# MCU.net
KiCad netlist of a schematic drawn in Altium Designer
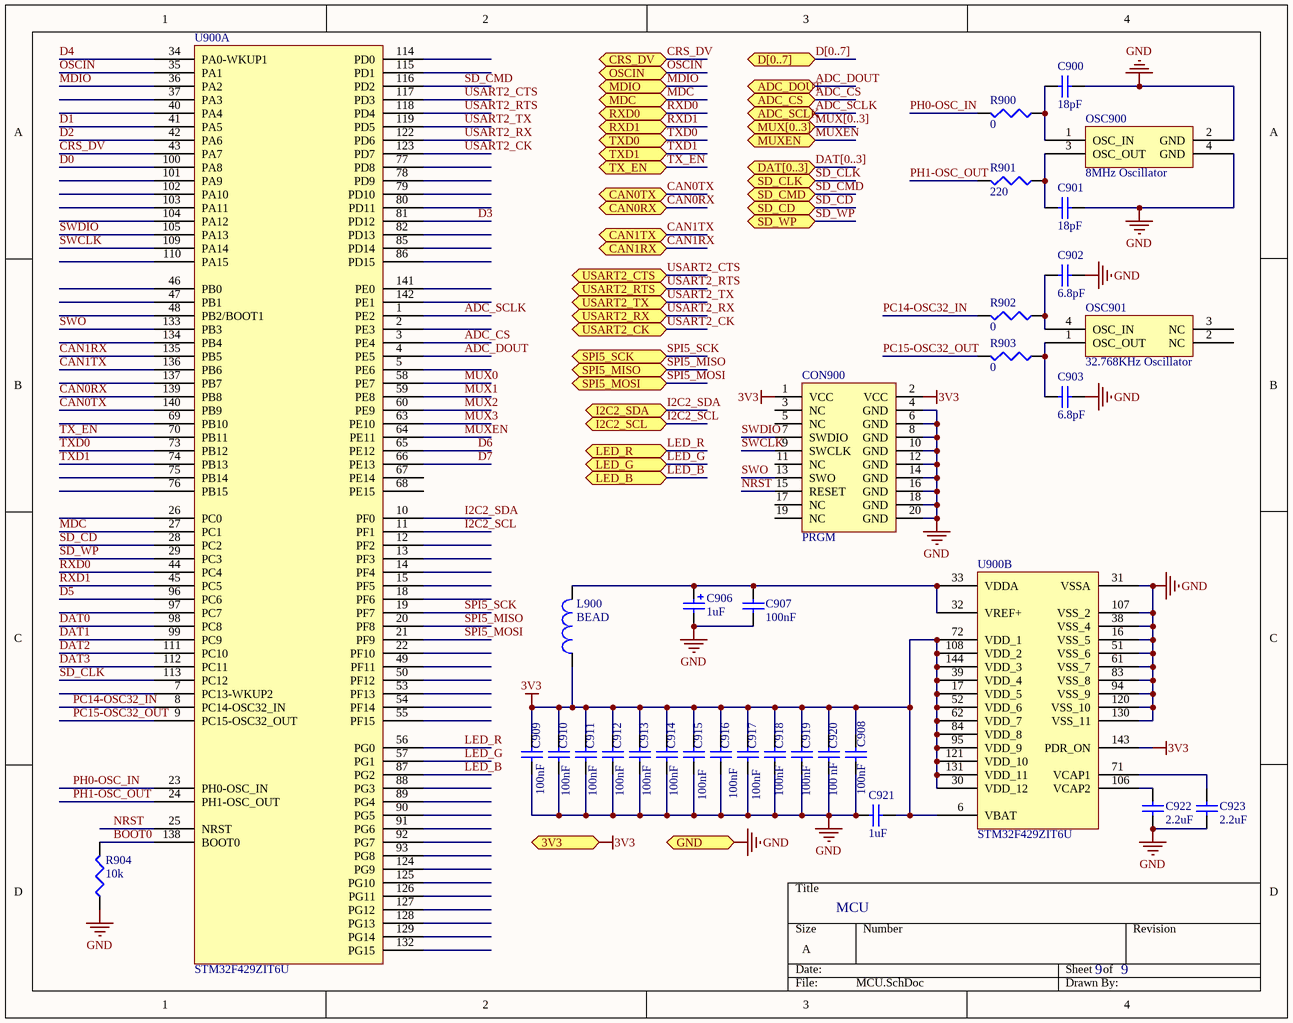
[diagram p0: MCU.SchDoc]

(export (version "E")
  (design (tool "Eeschema 10.0.6"))
  (components
    (comp (ref "C900")
      (value "18pF")
      (footprint "SMD0603")
      (description "Ceramic Chip Capacitor")
      (fields (field (name "Comment") "Cap"))
      (libsource (lib "Components") (part "Capacitor Ceramic"))
    )
    (comp (ref "C901")
      (value "18pF")
      (footprint "SMD0603")
      (description "Ceramic Chip Capacitor")
      (fields (field (name "Comment") "Cap"))
      (libsource (lib "Components") (part "Capacitor Ceramic"))
    )
    (comp (ref "C902")
      (value "6.8pF")
      (footprint "SMD0603")
      (description "Ceramic Chip Capacitor")
      (fields (field (name "Comment") "Cap"))
      (libsource (lib "Components") (part "Capacitor Ceramic"))
    )
    (comp (ref "C903")
      (value "6.8pF")
      (footprint "SMD0603")
      (description "Ceramic Chip Capacitor")
      (fields (field (name "Comment") "Cap"))
      (libsource (lib "Components") (part "Capacitor Ceramic"))
    )
    (comp (ref "C906")
      (value "1uF")
      (footprint "SMD1206 Polarized")
      (description "Polarized Capacitor (Surface Mount)")
      (fields (field (name "Comment") "Cap"))
      (libsource (lib "Components") (part "Capacitor Polarized"))
    )
    (comp (ref "C907")
      (value "100nF")
      (footprint "SMD0603")
      (description "Ceramic Chip Capacitor")
      (fields (field (name "Comment") "Cap"))
      (libsource (lib "Components") (part "Capacitor Ceramic"))
    )
    (comp (ref "C908")
      (value "100nF")
      (footprint "SMD0603")
      (description "Ceramic Chip Capacitor")
      (fields (field (name "Comment") "Cap"))
      (libsource (lib "Components") (part "Capacitor Ceramic"))
    )
    (comp (ref "C909")
      (value "100nF")
      (footprint "SMD0603")
      (description "Ceramic Chip Capacitor")
      (fields (field (name "Comment") "Cap"))
      (libsource (lib "Components") (part "Capacitor Ceramic"))
    )
    (comp (ref "C910")
      (value "100nF")
      (footprint "SMD0603")
      (description "Ceramic Chip Capacitor")
      (fields (field (name "Comment") "Cap"))
      (libsource (lib "Components") (part "Capacitor Ceramic"))
    )
    (comp (ref "C911")
      (value "100nF")
      (footprint "SMD0603")
      (description "Ceramic Chip Capacitor")
      (fields (field (name "Comment") "Cap"))
      (libsource (lib "Components") (part "Capacitor Ceramic"))
    )
    (comp (ref "C912")
      (value "100nF")
      (footprint "SMD0603")
      (description "Ceramic Chip Capacitor")
      (fields (field (name "Comment") "Cap"))
      (libsource (lib "Components") (part "Capacitor Ceramic"))
    )
    (comp (ref "C913")
      (value "100nF")
      (footprint "SMD0603")
      (description "Ceramic Chip Capacitor")
      (fields (field (name "Comment") "Cap"))
      (libsource (lib "Components") (part "Capacitor Ceramic"))
    )
    (comp (ref "C914")
      (value "100nF")
      (footprint "SMD0603")
      (description "Ceramic Chip Capacitor")
      (fields (field (name "Comment") "Cap"))
      (libsource (lib "Components") (part "Capacitor Ceramic"))
    )
    (comp (ref "C915")
      (value "100nF")
      (footprint "SMD0603")
      (description "Ceramic Chip Capacitor")
      (fields (field (name "Comment") "Cap"))
      (libsource (lib "Components") (part "Capacitor Ceramic"))
    )
    (comp (ref "C916")
      (value "100nF")
      (footprint "SMD0603")
      (description "Ceramic Chip Capacitor")
      (fields (field (name "Comment") "Cap"))
      (libsource (lib "Components") (part "Capacitor Ceramic"))
    )
    (comp (ref "C917")
      (value "100nF")
      (footprint "SMD0603")
      (description "Ceramic Chip Capacitor")
      (fields (field (name "Comment") "Cap"))
      (libsource (lib "Components") (part "Capacitor Ceramic"))
    )
    (comp (ref "C918")
      (value "100nF")
      (footprint "SMD0603")
      (description "Ceramic Chip Capacitor")
      (fields (field (name "Comment") "Cap"))
      (libsource (lib "Components") (part "Capacitor Ceramic"))
    )
    (comp (ref "C919")
      (value "100nF")
      (footprint "SMD0603")
      (description "Ceramic Chip Capacitor")
      (fields (field (name "Comment") "Cap"))
      (libsource (lib "Components") (part "Capacitor Ceramic"))
    )
    (comp (ref "C920")
      (value "100 nF")
      (footprint "SMD0603")
      (description "Ceramic Chip Capacitor")
      (fields (field (name "Comment") "Cap"))
      (libsource (lib "Components") (part "Capacitor Ceramic"))
    )
    (comp (ref "C921")
      (value "1uF")
      (footprint "SMD0805")
      (description "Ceramic Chip Capacitor")
      (fields (field (name "Comment") "Cap"))
      (libsource (lib "Components") (part "Capacitor Ceramic"))
    )
    (comp (ref "C922")
      (value "2.2uF")
      (footprint "SMD1206")
      (description "Ceramic Chip Capacitor")
      (fields (field (name "Comment") "Cap"))
      (libsource (lib "Components") (part "Capacitor Ceramic"))
    )
    (comp (ref "C923")
      (value "2.2uF")
      (footprint "SMD1206")
      (description "Ceramic Chip Capacitor")
      (fields (field (name "Comment") "Cap"))
      (libsource (lib "Components") (part "Capacitor Ceramic"))
    )
    (comp (ref "CON900")
      (value "PRGM")
      (footprint "JTAG/SWO-20PIN")
      (libsource (lib "Components") (part "JTAG/SWO-20PIN"))
    )
    (comp (ref "L900")
      (value "BEAD")
      (footprint "SMD0603")
      (description "Ferrite Bead")
      (fields (field (name "PART") "BK1608HS601-TV"))
      (libsource (lib "Components") (part "Chip Ferrite Bead"))
    )
    (comp (ref "OSC900")
      (value "8MHz Oscillator")
      (footprint "ABMM2-OSC")
      (libsource (lib "Components") (part "ABMM2-8.000MHZ-E2-T"))
    )
    (comp (ref "OSC901")
      (value "32.768KHz Oscillator")
      (footprint "MC-306-OSC")
      (description "32.7680kHz Oscillator")
      (libsource (lib "Components") (part "MC-306 32.768K-E3"))
    )
    (comp (ref "R900")
      (value "0")
      (footprint "SMD0603")
      (description "Resistor")
      (fields (field (name "Comment") "Res"))
      (libsource (lib "Components") (part "Resistor"))
    )
    (comp (ref "R901")
      (value "220")
      (footprint "SMD0603")
      (description "Resistor")
      (fields (field (name "Comment") "Res"))
      (libsource (lib "Components") (part "Resistor"))
    )
    (comp (ref "R902")
      (value "0")
      (footprint "SMD0603")
      (description "Resistor")
      (fields (field (name "Comment") "Res"))
      (libsource (lib "Components") (part "Resistor"))
    )
    (comp (ref "R903")
      (value "0")
      (footprint "SMD0603")
      (description "Resistor")
      (fields (field (name "Comment") "Res"))
      (libsource (lib "Components") (part "Resistor"))
    )
    (comp (ref "R904")
      (value "10k")
      (footprint "SMD0603")
      (description "Resistor")
      (fields (field (name "Comment") "Res"))
      (libsource (lib "Components") (part "Resistor"))
    )
    (comp (ref "U900")
      (value "STM32F429ZIT6U")
      (footprint "LQPF144")
      (libsource (lib "Components") (part "STM32F429ZIT6U"))
    )
  )
  (nets
    (net (code "1") (name "/ADC_CS") (class "Default")
      (node (ref "U900") (pin "3") (pinfunction "PE4_3") (pintype "passive"))
    )
    (net (code "2") (name "/ADC_DOUT") (class "Default")
      (node (ref "U900") (pin "4") (pinfunction "PE5_4") (pintype "passive"))
    )
    (net (code "3") (name "/ADC_SCLK") (class "Default")
      (node (ref "U900") (pin "1") (pinfunction "PE2_1") (pintype "passive"))
    )
    (net (code "4") (name "/BOOT0") (class "Default")
      (node (ref "R904") (pin "2") (pinfunction "2_2") (pintype "passive"))
      (node (ref "U900") (pin "138") (pinfunction "BOOT0_138") (pintype "passive"))
    )
    (net (code "5") (name "/CAN0RX") (class "Default")
      (node (ref "U900") (pin "139") (pinfunction "PB8_139") (pintype "passive"))
    )
    (net (code "6") (name "/CAN0TX") (class "Default")
      (node (ref "U900") (pin "140") (pinfunction "PB9_140") (pintype "passive"))
    )
    (net (code "7") (name "/CAN1RX") (class "Default")
      (node (ref "U900") (pin "135") (pinfunction "PB5_135") (pintype "passive"))
    )
    (net (code "8") (name "/CAN1TX") (class "Default")
      (node (ref "U900") (pin "136") (pinfunction "PB6_136") (pintype "passive"))
    )
    (net (code "9") (name "/CRS_DV") (class "Default")
      (node (ref "U900") (pin "43") (pinfunction "PA7_43") (pintype "passive"))
    )
    (net (code "10") (name "/D0") (class "Default")
      (node (ref "U900") (pin "100") (pinfunction "PA8_100") (pintype "passive"))
    )
    (net (code "11") (name "/D1") (class "Default")
      (node (ref "U900") (pin "41") (pinfunction "PA5_41") (pintype "passive"))
    )
    (net (code "12") (name "/D2") (class "Default")
      (node (ref "U900") (pin "42") (pinfunction "PA6_42") (pintype "passive"))
    )
    (net (code "13") (name "/D3") (class "Default")
      (node (ref "U900") (pin "81") (pinfunction "PD12_81") (pintype "passive"))
    )
    (net (code "14") (name "/D4") (class "Default")
      (node (ref "U900") (pin "34") (pinfunction "PA0-WKUP1_34") (pintype "passive"))
    )
    (net (code "15") (name "/D5") (class "Default")
      (node (ref "U900") (pin "96") (pinfunction "PC6_96") (pintype "passive"))
    )
    (net (code "16") (name "/D6") (class "Default")
      (node (ref "U900") (pin "65") (pinfunction "PE12_65") (pintype "passive"))
    )
    (net (code "17") (name "/D7") (class "Default")
      (node (ref "U900") (pin "66") (pinfunction "PE13_66") (pintype "passive"))
    )
    (net (code "18") (name "/DAT0") (class "Default")
      (node (ref "U900") (pin "98") (pinfunction "PC8_98") (pintype "passive"))
    )
    (net (code "19") (name "/DAT1") (class "Default")
      (node (ref "U900") (pin "99") (pinfunction "PC9_99") (pintype "passive"))
    )
    (net (code "20") (name "/DAT2") (class "Default")
      (node (ref "U900") (pin "111") (pinfunction "PC10_111") (pintype "passive"))
    )
    (net (code "21") (name "/DAT3") (class "Default")
      (node (ref "U900") (pin "112") (pinfunction "PC11_112") (pintype "passive"))
    )
    (net (code "24") (name "/I2C2_SCL") (class "Default")
      (node (ref "U900") (pin "11") (pinfunction "PF1_11") (pintype "passive"))
    )
    (net (code "25") (name "/I2C2_SDA") (class "Default")
      (node (ref "U900") (pin "10") (pinfunction "PF0_10") (pintype "passive"))
    )
    (net (code "26") (name "/LED_B") (class "Default")
      (node (ref "U900") (pin "87") (pinfunction "PG2_87") (pintype "passive"))
    )
    (net (code "27") (name "/LED_G") (class "Default")
      (node (ref "U900") (pin "57") (pinfunction "PG1_57") (pintype "passive"))
    )
    (net (code "28") (name "/LED_R") (class "Default")
      (node (ref "U900") (pin "56") (pinfunction "PG0_56") (pintype "passive"))
    )
    (net (code "29") (name "/MDC") (class "Default")
      (node (ref "U900") (pin "27") (pinfunction "PC1_27") (pintype "passive"))
    )
    (net (code "30") (name "/MDIO") (class "Default")
      (node (ref "U900") (pin "36") (pinfunction "PA2_36") (pintype "passive"))
    )
    (net (code "31") (name "/MUX0") (class "Default")
      (node (ref "U900") (pin "58") (pinfunction "PE7_58") (pintype "passive"))
    )
    (net (code "32") (name "/MUX1") (class "Default")
      (node (ref "U900") (pin "59") (pinfunction "PE8_59") (pintype "passive"))
    )
    (net (code "33") (name "/MUX2") (class "Default")
      (node (ref "U900") (pin "60") (pinfunction "PE9_60") (pintype "passive"))
    )
    (net (code "34") (name "/MUX3") (class "Default")
      (node (ref "U900") (pin "63") (pinfunction "PE10_63") (pintype "passive"))
    )
    (net (code "35") (name "/MUXEN") (class "Default")
      (node (ref "U900") (pin "64") (pinfunction "PE11_64") (pintype "passive"))
    )
    (net (code "37") (name "/NRST") (class "Default")
      (node (ref "CON900") (pin "15") (pinfunction "RESET_15") (pintype "passive"))
      (node (ref "U900") (pin "25") (pinfunction "NRST_25") (pintype "passive"))
    )
    (net (code "38") (name "/OSCIN") (class "Default")
      (node (ref "U900") (pin "35") (pinfunction "PA1_35") (pintype "passive"))
    )
    (net (code "39") (name "/PC14-OSC32_IN") (class "Default")
      (node (ref "R902") (pin "2") (pinfunction "2_2") (pintype "passive"))
      (node (ref "U900") (pin "8") (pinfunction "PC14-OSC32_IN_8") (pintype "passive"))
    )
    (net (code "40") (name "/PC15-OSC32_OUT") (class "Default")
      (node (ref "R903") (pin "2") (pinfunction "2_2") (pintype "passive"))
      (node (ref "U900") (pin "9") (pinfunction "PC15-OSC32_OUT_9") (pintype "passive"))
    )
    (net (code "41") (name "/PH0-OSC_IN") (class "Default")
      (node (ref "R900") (pin "2") (pinfunction "2_2") (pintype "passive"))
      (node (ref "U900") (pin "23") (pinfunction "PH0-OSC_IN_23") (pintype "passive"))
    )
    (net (code "42") (name "/PH1-OSC_OUT") (class "Default")
      (node (ref "R901") (pin "2") (pinfunction "2_2") (pintype "passive"))
      (node (ref "U900") (pin "24") (pinfunction "PH1-OSC_OUT_24") (pintype "passive"))
    )
    (net (code "43") (name "/RXD0") (class "Default")
      (node (ref "U900") (pin "44") (pinfunction "PC4_44") (pintype "passive"))
    )
    (net (code "44") (name "/RXD1") (class "Default")
      (node (ref "U900") (pin "45") (pinfunction "PC5_45") (pintype "passive"))
    )
    (net (code "45") (name "/SD_CD") (class "Default")
      (node (ref "U900") (pin "28") (pinfunction "PC2_28") (pintype "passive"))
    )
    (net (code "46") (name "/SD_CLK") (class "Default")
      (node (ref "U900") (pin "113") (pinfunction "PC12_113") (pintype "passive"))
    )
    (net (code "47") (name "/SD_CMD") (class "Default")
      (node (ref "U900") (pin "116") (pinfunction "PD2_116") (pintype "passive"))
    )
    (net (code "48") (name "/SD_WP") (class "Default")
      (node (ref "U900") (pin "29") (pinfunction "PC3_29") (pintype "passive"))
    )
    (net (code "49") (name "/SPI5_MISO") (class "Default")
      (node (ref "U900") (pin "20") (pinfunction "PF8_20") (pintype "passive"))
    )
    (net (code "50") (name "/SPI5_MOSI") (class "Default")
      (node (ref "U900") (pin "21") (pinfunction "PF9_21") (pintype "passive"))
    )
    (net (code "51") (name "/SPI5_SCK") (class "Default")
      (node (ref "U900") (pin "19") (pinfunction "PF7_19") (pintype "passive"))
    )
    (net (code "52") (name "/SWCLK") (class "Default")
      (node (ref "CON900") (pin "9") (pinfunction "SWCLK_9") (pintype "passive"))
      (node (ref "U900") (pin "109") (pinfunction "PA14_109") (pintype "passive"))
    )
    (net (code "53") (name "/SWDIO") (class "Default")
      (node (ref "CON900") (pin "7") (pinfunction "SWDIO_7") (pintype "passive"))
      (node (ref "U900") (pin "105") (pinfunction "PA13_105") (pintype "passive"))
    )
    (net (code "54") (name "/SWO") (class "Default")
      (node (ref "CON900") (pin "13") (pinfunction "SWO_13") (pintype "passive"))
      (node (ref "U900") (pin "133") (pinfunction "PB3_133") (pintype "passive"))
    )
    (net (code "55") (name "/TXD0") (class "Default")
      (node (ref "U900") (pin "73") (pinfunction "PB12_73") (pintype "passive"))
    )
    (net (code "56") (name "/TXD1") (class "Default")
      (node (ref "U900") (pin "74") (pinfunction "PB13_74") (pintype "passive"))
    )
    (net (code "57") (name "/TX_EN") (class "Default")
      (node (ref "U900") (pin "70") (pinfunction "PB11_70") (pintype "passive"))
    )
    (net (code "58") (name "/USART2_CK") (class "Default")
      (node (ref "U900") (pin "123") (pinfunction "PD7_123") (pintype "passive"))
    )
    (net (code "59") (name "/USART2_CTS") (class "Default")
      (node (ref "U900") (pin "117") (pinfunction "PD3_117") (pintype "passive"))
    )
    (net (code "60") (name "/USART2_RTS") (class "Default")
      (node (ref "U900") (pin "118") (pinfunction "PD4_118") (pintype "passive"))
    )
    (net (code "61") (name "/USART2_RX") (class "Default")
      (node (ref "U900") (pin "122") (pinfunction "PD6_122") (pintype "passive"))
    )
    (net (code "62") (name "/USART2_TX") (class "Default")
      (node (ref "U900") (pin "119") (pinfunction "PD5_119") (pintype "passive"))
    )
    (net (code "63") (name "3V3") (class "Default")
      (node (ref "C908") (pin "1") (pinfunction "1_1") (pintype "passive"))
      (node (ref "C909") (pin "2") (pinfunction "2_2") (pintype "passive"))
      (node (ref "C910") (pin "2") (pinfunction "2_2") (pintype "passive"))
      (node (ref "C911") (pin "2") (pinfunction "2_2") (pintype "passive"))
      (node (ref "C912") (pin "2") (pinfunction "2_2") (pintype "passive"))
      (node (ref "C913") (pin "2") (pinfunction "2_2") (pintype "passive"))
      (node (ref "C914") (pin "2") (pinfunction "2_2") (pintype "passive"))
      (node (ref "C915") (pin "2") (pinfunction "2_2") (pintype "passive"))
      (node (ref "C916") (pin "2") (pinfunction "2_2") (pintype "passive"))
      (node (ref "C917") (pin "2") (pinfunction "2_2") (pintype "passive"))
      (node (ref "C918") (pin "2") (pinfunction "2_2") (pintype "passive"))
      (node (ref "C919") (pin "2") (pinfunction "2_2") (pintype "passive"))
      (node (ref "C920") (pin "2") (pinfunction "2_2") (pintype "passive"))
      (node (ref "C921") (pin "1") (pinfunction "1_1") (pintype "passive"))
      (node (ref "CON900") (pin "1") (pinfunction "VCC_1") (pintype "passive"))
      (node (ref "CON900") (pin "2") (pinfunction "VCC_2") (pintype "passive"))
      (node (ref "L900") (pin "1") (pintype "passive"))
      (node (ref "U900") (pin "108") (pinfunction "VDD_2_108") (pintype "passive"))
      (node (ref "U900") (pin "121") (pinfunction "VDD_10_121") (pintype "passive"))
      (node (ref "U900") (pin "131") (pinfunction "VDD_11_131") (pintype "passive"))
      (node (ref "U900") (pin "143") (pinfunction "PDR_ON_143") (pintype "passive"))
      (node (ref "U900") (pin "144") (pinfunction "VDD_3_144") (pintype "passive"))
      (node (ref "U900") (pin "17") (pinfunction "VDD_5_17") (pintype "passive"))
      (node (ref "U900") (pin "30") (pinfunction "VDD_12_30") (pintype "passive"))
      (node (ref "U900") (pin "39") (pinfunction "VDD_4_39") (pintype "passive"))
      (node (ref "U900") (pin "52") (pinfunction "VDD_6_52") (pintype "passive"))
      (node (ref "U900") (pin "6") (pinfunction "VBAT_6") (pintype "passive"))
      (node (ref "U900") (pin "62") (pinfunction "VDD_7_62") (pintype "passive"))
      (node (ref "U900") (pin "72") (pinfunction "VDD_1_72") (pintype "passive"))
      (node (ref "U900") (pin "84") (pinfunction "VDD_8_84") (pintype "passive"))
      (node (ref "U900") (pin "95") (pinfunction "VDD_9_95") (pintype "passive"))
    )
    (net (code "64") (name "GND") (class "Default")
      (node (ref "C900") (pin "1") (pinfunction "1_1") (pintype "passive"))
      (node (ref "C901") (pin "1") (pinfunction "1_1") (pintype "passive"))
      (node (ref "C902") (pin "1") (pinfunction "1_1") (pintype "passive"))
      (node (ref "C903") (pin "1") (pinfunction "1_1") (pintype "passive"))
      (node (ref "C906") (pin "2") (pinfunction "2_2") (pintype "passive"))
      (node (ref "C907") (pin "2") (pinfunction "2_2") (pintype "passive"))
      (node (ref "C908") (pin "2") (pinfunction "2_2") (pintype "passive"))
      (node (ref "C909") (pin "1") (pinfunction "1_1") (pintype "passive"))
      (node (ref "C910") (pin "1") (pinfunction "1_1") (pintype "passive"))
      (node (ref "C911") (pin "1") (pinfunction "1_1") (pintype "passive"))
      (node (ref "C912") (pin "1") (pinfunction "1_1") (pintype "passive"))
      (node (ref "C913") (pin "1") (pinfunction "1_1") (pintype "passive"))
      (node (ref "C914") (pin "1") (pinfunction "1_1") (pintype "passive"))
      (node (ref "C915") (pin "1") (pinfunction "1_1") (pintype "passive"))
      (node (ref "C916") (pin "1") (pinfunction "1_1") (pintype "passive"))
      (node (ref "C917") (pin "1") (pinfunction "1_1") (pintype "passive"))
      (node (ref "C918") (pin "1") (pinfunction "1_1") (pintype "passive"))
      (node (ref "C919") (pin "1") (pinfunction "1_1") (pintype "passive"))
      (node (ref "C920") (pin "1") (pinfunction "1_1") (pintype "passive"))
      (node (ref "C921") (pin "2") (pinfunction "2_2") (pintype "passive"))
      (node (ref "C922") (pin "1") (pinfunction "1_1") (pintype "passive"))
      (node (ref "C923") (pin "1") (pinfunction "1_1") (pintype "passive"))
      (node (ref "CON900") (pin "10") (pinfunction "GND_10") (pintype "passive"))
      (node (ref "CON900") (pin "12") (pinfunction "GND_12") (pintype "passive"))
      (node (ref "CON900") (pin "14") (pinfunction "GND_14") (pintype "passive"))
      (node (ref "CON900") (pin "16") (pinfunction "GND_16") (pintype "passive"))
      (node (ref "CON900") (pin "18") (pinfunction "GND_18") (pintype "passive"))
      (node (ref "CON900") (pin "20") (pinfunction "GND_20") (pintype "passive"))
      (node (ref "CON900") (pin "4") (pinfunction "GND_4") (pintype "passive"))
      (node (ref "CON900") (pin "6") (pinfunction "GND_6") (pintype "passive"))
      (node (ref "CON900") (pin "8") (pinfunction "GND_8") (pintype "passive"))
      (node (ref "OSC900") (pin "2") (pinfunction "GND_2") (pintype "passive"))
      (node (ref "OSC900") (pin "4") (pinfunction "GND_4") (pintype "passive"))
      (node (ref "R904") (pin "1") (pinfunction "1_1") (pintype "passive"))
      (node (ref "U900") (pin "107") (pinfunction "VSS_2_107") (pintype "passive"))
      (node (ref "U900") (pin "120") (pinfunction "VSS_10_120") (pintype "passive"))
      (node (ref "U900") (pin "130") (pinfunction "VSS_11_130") (pintype "passive"))
      (node (ref "U900") (pin "16") (pinfunction "VSS_5_16") (pintype "passive"))
      (node (ref "U900") (pin "31") (pinfunction "VSSA_31") (pintype "passive"))
      (node (ref "U900") (pin "38") (pinfunction "VSS_4_38") (pintype "passive"))
      (node (ref "U900") (pin "51") (pinfunction "VSS_6_51") (pintype "passive"))
      (node (ref "U900") (pin "61") (pinfunction "VSS_7_61") (pintype "passive"))
      (node (ref "U900") (pin "83") (pinfunction "VSS_8_83") (pintype "passive"))
      (node (ref "U900") (pin "94") (pinfunction "VSS_9_94") (pintype "passive"))
    )
    (net (code "65") (name "Net-(OSC900-OSC_IN)") (class "Default")
      (node (ref "C900") (pin "2") (pinfunction "2_2") (pintype "passive"))
      (node (ref "OSC900") (pin "1") (pinfunction "OSC_IN_1") (pintype "passive"))
      (node (ref "R900") (pin "1") (pinfunction "1_1") (pintype "passive"))
    )
    (net (code "66") (name "Net-(OSC900-OSC_OUT)") (class "Default")
      (node (ref "C901") (pin "2") (pinfunction "2_2") (pintype "passive"))
      (node (ref "OSC900") (pin "3") (pinfunction "OSC_OUT_3") (pintype "passive"))
      (node (ref "R901") (pin "1") (pinfunction "1_1") (pintype "passive"))
    )
    (net (code "67") (name "Net-(OSC901-OSC_IN)") (class "Default")
      (node (ref "C902") (pin "2") (pinfunction "2_2") (pintype "passive"))
      (node (ref "OSC901") (pin "4") (pinfunction "OSC_IN_4") (pintype "passive"))
      (node (ref "R902") (pin "1") (pinfunction "1_1") (pintype "passive"))
    )
    (net (code "68") (name "Net-(OSC901-OSC_OUT)") (class "Default")
      (node (ref "C903") (pin "2") (pinfunction "2_2") (pintype "passive"))
      (node (ref "OSC901") (pin "1") (pinfunction "OSC_OUT_1") (pintype "passive"))
      (node (ref "R903") (pin "1") (pinfunction "1_1") (pintype "passive"))
    )
    (net (code "69") (name "Net-(U900B-VCAP1)") (class "Default")
      (node (ref "C923") (pin "2") (pinfunction "2_2") (pintype "passive"))
      (node (ref "U900") (pin "71") (pinfunction "VCAP1_71") (pintype "passive"))
    )
    (net (code "70") (name "Net-(U900B-VCAP2)") (class "Default")
      (node (ref "C922") (pin "2") (pinfunction "2_2") (pintype "passive"))
      (node (ref "U900") (pin "106") (pinfunction "VCAP2_106") (pintype "passive"))
    )
    (net (code "71") (name "Net-(U900B-VDDA)") (class "Default")
      (node (ref "C906") (pin "1") (pinfunction "1_1") (pintype "passive"))
      (node (ref "C907") (pin "1") (pinfunction "1_1") (pintype "passive"))
      (node (ref "L900") (pin "2") (pintype "passive"))
      (node (ref "U900") (pin "32") (pinfunction "VREF+_32") (pintype "passive"))
      (node (ref "U900") (pin "33") (pinfunction "VDDA_33") (pintype "passive"))
    )
    (net (code "72") (name "unconnected-(CON900-NC-Pad3)") (class "Default")
      (node (ref "CON900") (pin "3") (pinfunction "NC_3") (pintype "passive"))
    )
    (net (code "73") (name "unconnected-(CON900-NC-Pad5)") (class "Default")
      (node (ref "CON900") (pin "5") (pinfunction "NC_5") (pintype "passive"))
    )
    (net (code "74") (name "unconnected-(CON900-NC-Pad11)") (class "Default")
      (node (ref "CON900") (pin "11") (pinfunction "NC_11") (pintype "passive"))
    )
    (net (code "75") (name "unconnected-(CON900-NC-Pad17)") (class "Default")
      (node (ref "CON900") (pin "17") (pinfunction "NC_17") (pintype "passive"))
    )
    (net (code "76") (name "unconnected-(CON900-NC-Pad19)") (class "Default")
      (node (ref "CON900") (pin "19") (pinfunction "NC_19") (pintype "passive"))
    )
    (net (code "77") (name "unconnected-(OSC901-NC-Pad2)") (class "Default")
      (node (ref "OSC901") (pin "2") (pinfunction "NC_2") (pintype "passive"))
    )
    (net (code "78") (name "unconnected-(OSC901-NC-Pad3)") (class "Default")
      (node (ref "OSC901") (pin "3") (pinfunction "NC_3") (pintype "passive"))
    )
    (net (code "79") (name "unconnected-(U900A-PA3-Pad37)") (class "Default")
      (node (ref "U900") (pin "37") (pinfunction "PA3_37") (pintype "passive"))
    )
    (net (code "80") (name "unconnected-(U900A-PA4-Pad40)") (class "Default")
      (node (ref "U900") (pin "40") (pinfunction "PA4_40") (pintype "passive"))
    )
    (net (code "81") (name "unconnected-(U900A-PA9-Pad101)") (class "Default")
      (node (ref "U900") (pin "101") (pinfunction "PA9_101") (pintype "passive"))
    )
    (net (code "82") (name "unconnected-(U900A-PA10-Pad102)") (class "Default")
      (node (ref "U900") (pin "102") (pinfunction "PA10_102") (pintype "passive"))
    )
    (net (code "83") (name "unconnected-(U900A-PA11-Pad103)") (class "Default")
      (node (ref "U900") (pin "103") (pinfunction "PA11_103") (pintype "passive"))
    )
    (net (code "84") (name "unconnected-(U900A-PA12-Pad104)") (class "Default")
      (node (ref "U900") (pin "104") (pinfunction "PA12_104") (pintype "passive"))
    )
    (net (code "85") (name "unconnected-(U900A-PA15-Pad110)") (class "Default")
      (node (ref "U900") (pin "110") (pinfunction "PA15_110") (pintype "passive"))
    )
    (net (code "86") (name "unconnected-(U900A-PB0-Pad46)") (class "Default")
      (node (ref "U900") (pin "46") (pinfunction "PB0_46") (pintype "passive"))
    )
    (net (code "87") (name "unconnected-(U900A-PB1-Pad47)") (class "Default")
      (node (ref "U900") (pin "47") (pinfunction "PB1_47") (pintype "passive"))
    )
    (net (code "88") (name "unconnected-(U900A-PB2{slash}BOOT1-Pad48)") (class "Default")
      (node (ref "U900") (pin "48") (pinfunction "PB2/BOOT1_48") (pintype "passive"))
    )
    (net (code "89") (name "unconnected-(U900A-PB4-Pad134)") (class "Default")
      (node (ref "U900") (pin "134") (pinfunction "PB4_134") (pintype "passive"))
    )
    (net (code "90") (name "unconnected-(U900A-PB7-Pad137)") (class "Default")
      (node (ref "U900") (pin "137") (pinfunction "PB7_137") (pintype "passive"))
    )
    (net (code "91") (name "unconnected-(U900A-PB10-Pad69)") (class "Default")
      (node (ref "U900") (pin "69") (pinfunction "PB10_69") (pintype "passive"))
    )
    (net (code "92") (name "unconnected-(U900A-PB14-Pad75)") (class "Default")
      (node (ref "U900") (pin "75") (pinfunction "PB14_75") (pintype "passive"))
    )
    (net (code "93") (name "unconnected-(U900A-PB15-Pad76)") (class "Default")
      (node (ref "U900") (pin "76") (pinfunction "PB15_76") (pintype "passive"))
    )
    (net (code "94") (name "unconnected-(U900A-PC0-Pad26)") (class "Default")
      (node (ref "U900") (pin "26") (pinfunction "PC0_26") (pintype "passive"))
    )
    (net (code "95") (name "unconnected-(U900A-PC7-Pad97)") (class "Default")
      (node (ref "U900") (pin "97") (pinfunction "PC7_97") (pintype "passive"))
    )
    (net (code "96") (name "unconnected-(U900A-PC13-WKUP2-Pad7)") (class "Default")
      (node (ref "U900") (pin "7") (pinfunction "PC13-WKUP2_7") (pintype "passive"))
    )
    (net (code "97") (name "unconnected-(U900A-PD0-Pad114)") (class "Default")
      (node (ref "U900") (pin "114") (pinfunction "PD0_114") (pintype "passive"))
    )
    (net (code "98") (name "unconnected-(U900A-PD1-Pad115)") (class "Default")
      (node (ref "U900") (pin "115") (pinfunction "PD1_115") (pintype "passive"))
    )
    (net (code "99") (name "unconnected-(U900A-PD8-Pad77)") (class "Default")
      (node (ref "U900") (pin "77") (pinfunction "PD8_77") (pintype "passive"))
    )
    (net (code "100") (name "unconnected-(U900A-PD9-Pad78)") (class "Default")
      (node (ref "U900") (pin "78") (pinfunction "PD9_78") (pintype "passive"))
    )
    (net (code "101") (name "unconnected-(U900A-PD10-Pad79)") (class "Default")
      (node (ref "U900") (pin "79") (pinfunction "PD10_79") (pintype "passive"))
    )
    (net (code "102") (name "unconnected-(U900A-PD11-Pad80)") (class "Default")
      (node (ref "U900") (pin "80") (pinfunction "PD11_80") (pintype "passive"))
    )
    (net (code "103") (name "unconnected-(U900A-PD13-Pad82)") (class "Default")
      (node (ref "U900") (pin "82") (pinfunction "PD13_82") (pintype "passive"))
    )
    (net (code "104") (name "unconnected-(U900A-PD14-Pad85)") (class "Default")
      (node (ref "U900") (pin "85") (pinfunction "PD14_85") (pintype "passive"))
    )
    (net (code "105") (name "unconnected-(U900A-PD15-Pad86)") (class "Default")
      (node (ref "U900") (pin "86") (pinfunction "PD15_86") (pintype "passive"))
    )
    (net (code "106") (name "unconnected-(U900A-PE0-Pad141)") (class "Default")
      (node (ref "U900") (pin "141") (pinfunction "PE0_141") (pintype "passive"))
    )
    (net (code "107") (name "unconnected-(U900A-PE1-Pad142)") (class "Default")
      (node (ref "U900") (pin "142") (pinfunction "PE1_142") (pintype "passive"))
    )
    (net (code "108") (name "unconnected-(U900A-PE3-Pad2)") (class "Default")
      (node (ref "U900") (pin "2") (pinfunction "PE3_2") (pintype "passive"))
    )
    (net (code "109") (name "unconnected-(U900A-PE6-Pad5)") (class "Default")
      (node (ref "U900") (pin "5") (pinfunction "PE6_5") (pintype "passive"))
    )
    (net (code "110") (name "unconnected-(U900A-PE14-Pad67)") (class "Default")
      (node (ref "U900") (pin "67") (pinfunction "PE14_67") (pintype "passive"))
    )
    (net (code "111") (name "unconnected-(U900A-PE15-Pad68)") (class "Default")
      (node (ref "U900") (pin "68") (pinfunction "PE15_68") (pintype "passive"))
    )
    (net (code "112") (name "unconnected-(U900A-PF2-Pad12)") (class "Default")
      (node (ref "U900") (pin "12") (pinfunction "PF2_12") (pintype "passive"))
    )
    (net (code "113") (name "unconnected-(U900A-PF3-Pad13)") (class "Default")
      (node (ref "U900") (pin "13") (pinfunction "PF3_13") (pintype "passive"))
    )
    (net (code "114") (name "unconnected-(U900A-PF4-Pad14)") (class "Default")
      (node (ref "U900") (pin "14") (pinfunction "PF4_14") (pintype "passive"))
    )
    (net (code "115") (name "unconnected-(U900A-PF5-Pad15)") (class "Default")
      (node (ref "U900") (pin "15") (pinfunction "PF5_15") (pintype "passive"))
    )
    (net (code "116") (name "unconnected-(U900A-PF6-Pad18)") (class "Default")
      (node (ref "U900") (pin "18") (pinfunction "PF6_18") (pintype "passive"))
    )
    (net (code "117") (name "unconnected-(U900A-PF10-Pad22)") (class "Default")
      (node (ref "U900") (pin "22") (pinfunction "PF10_22") (pintype "passive"))
    )
    (net (code "118") (name "unconnected-(U900A-PF11-Pad49)") (class "Default")
      (node (ref "U900") (pin "49") (pinfunction "PF11_49") (pintype "passive"))
    )
    (net (code "119") (name "unconnected-(U900A-PF12-Pad50)") (class "Default")
      (node (ref "U900") (pin "50") (pinfunction "PF12_50") (pintype "passive"))
    )
    (net (code "120") (name "unconnected-(U900A-PF13-Pad53)") (class "Default")
      (node (ref "U900") (pin "53") (pinfunction "PF13_53") (pintype "passive"))
    )
    (net (code "121") (name "unconnected-(U900A-PF14-Pad54)") (class "Default")
      (node (ref "U900") (pin "54") (pinfunction "PF14_54") (pintype "passive"))
    )
    (net (code "122") (name "unconnected-(U900A-PF15-Pad55)") (class "Default")
      (node (ref "U900") (pin "55") (pinfunction "PF15_55") (pintype "passive"))
    )
    (net (code "123") (name "unconnected-(U900A-PG3-Pad88)") (class "Default")
      (node (ref "U900") (pin "88") (pinfunction "PG3_88") (pintype "passive"))
    )
    (net (code "124") (name "unconnected-(U900A-PG4-Pad89)") (class "Default")
      (node (ref "U900") (pin "89") (pinfunction "PG4_89") (pintype "passive"))
    )
    (net (code "125") (name "unconnected-(U900A-PG5-Pad90)") (class "Default")
      (node (ref "U900") (pin "90") (pinfunction "PG5_90") (pintype "passive"))
    )
    (net (code "126") (name "unconnected-(U900A-PG6-Pad91)") (class "Default")
      (node (ref "U900") (pin "91") (pinfunction "PG6_91") (pintype "passive"))
    )
    (net (code "127") (name "unconnected-(U900A-PG7-Pad92)") (class "Default")
      (node (ref "U900") (pin "92") (pinfunction "PG7_92") (pintype "passive"))
    )
    (net (code "128") (name "unconnected-(U900A-PG8-Pad93)") (class "Default")
      (node (ref "U900") (pin "93") (pinfunction "PG8_93") (pintype "passive"))
    )
    (net (code "129") (name "unconnected-(U900A-PG9-Pad124)") (class "Default")
      (node (ref "U900") (pin "124") (pinfunction "PG9_124") (pintype "passive"))
    )
    (net (code "130") (name "unconnected-(U900A-PG10-Pad125)") (class "Default")
      (node (ref "U900") (pin "125") (pinfunction "PG10_125") (pintype "passive"))
    )
    (net (code "131") (name "unconnected-(U900A-PG11-Pad126)") (class "Default")
      (node (ref "U900") (pin "126") (pinfunction "PG11_126") (pintype "passive"))
    )
    (net (code "132") (name "unconnected-(U900A-PG12-Pad127)") (class "Default")
      (node (ref "U900") (pin "127") (pinfunction "PG12_127") (pintype "passive"))
    )
    (net (code "133") (name "unconnected-(U900A-PG13-Pad128)") (class "Default")
      (node (ref "U900") (pin "128") (pinfunction "PG13_128") (pintype "passive"))
    )
    (net (code "134") (name "unconnected-(U900A-PG14-Pad129)") (class "Default")
      (node (ref "U900") (pin "129") (pinfunction "PG14_129") (pintype "passive"))
    )
    (net (code "135") (name "unconnected-(U900A-PG15-Pad132)") (class "Default")
      (node (ref "U900") (pin "132") (pinfunction "PG15_132") (pintype "passive"))
    )
  )
)
